# PeakShaver.net
KiCad netlist of a schematic drawn in EAGLE
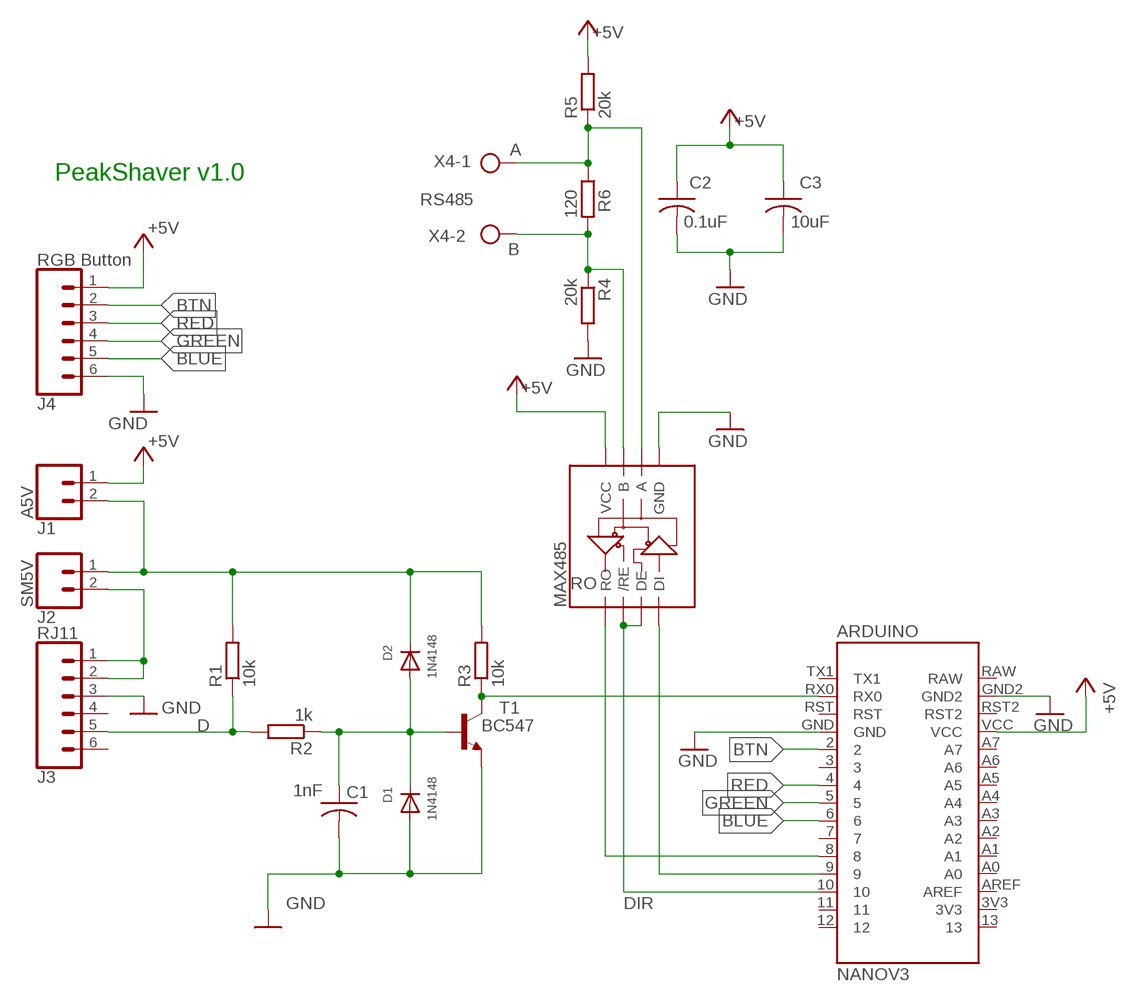
[diagram p0: schematic, sheet 1]

(export (version "E")
  (design (tool "Eeschema 10.0.6"))
  (components
    (comp (ref "ARDUINO")
      (value "NANOV3")
      (footprint "eagle-import:NANOV3")
      (libsource (lib "eagle-import") (part "NANOV3"))
    )
    (comp (ref "C1")
      (value "1nF")
      (footprint "eagle-import:C025-025X050")
      (libsource (lib "eagle-import") (part "C-US025-025X050"))
    )
    (comp (ref "C2")
      (value "0.1uF")
      (footprint "eagle-import:C025-025X050")
      (libsource (lib "eagle-import") (part "C-US025-025X050"))
    )
    (comp (ref "C3")
      (value "10uF")
      (footprint "eagle-import:CAP_RADIAL_2MM")
      (fields
        (field (name "DIGIKEY_PART_NUMBER") "P5178-ND")
        (field (name "MANUFACTURER") "Panasonic Electronic Components")
        (field (name "MPN") "ECA-1HM100")
        (field (name "CREATED_BY") "PCBLayout.com")
      )
      (libsource (lib "eagle-import") (part "ECA-1HM100"))
    )
    (comp (ref "D1")
      (value "1N4148")
      (footprint "eagle-import:DO-1N4148")
      (libsource (lib "eagle-import") (part "DIODEDO-1N4148"))
    )
    (comp (ref "D2")
      (value "1N4148")
      (footprint "eagle-import:DO-1N4148")
      (libsource (lib "eagle-import") (part "DIODEDO-1N4148"))
    )
    (comp (ref "J1")
      (value "A5V")
      (footprint "eagle-import:1X02")
      (libsource (lib "eagle-import") (part "CONN_02"))
    )
    (comp (ref "J2")
      (value "SM5V")
      (footprint "eagle-import:1X02")
      (libsource (lib "eagle-import") (part "CONN_02"))
    )
    (comp (ref "J3")
      (value "RJ11")
      (footprint "eagle-import:RJ11-6")
      (libsource (lib "eagle-import") (part "RJ11-6"))
    )
    (comp (ref "J4")
      (value "RGB Button")
      (footprint "eagle-import:1X06_LOCK")
      (libsource (lib "eagle-import") (part "CONN_06LOCK"))
    )
    (comp (ref "MAX485")
      (value "SPARKFUN-IC-COMMS_RS485")
      (footprint "eagle-import:TEXAS_DIL08")
      (libsource (lib "eagle-import") (part "SPARKFUN-IC-COMMS_RS485"))
    )
    (comp (ref "R1")
      (value "10k")
      (footprint "eagle-import:0207_10")
      (libsource (lib "eagle-import") (part "R-EU_0207/10"))
    )
    (comp (ref "R2")
      (value "1k")
      (footprint "eagle-import:0207_10")
      (libsource (lib "eagle-import") (part "R-EU_0207/10"))
    )
    (comp (ref "R3")
      (value "10k")
      (footprint "eagle-import:0207_10")
      (libsource (lib "eagle-import") (part "R-EU_0207/10"))
    )
    (comp (ref "R4")
      (value "20k")
      (footprint "eagle-import:0207_10")
      (libsource (lib "eagle-import") (part "R-EU_0207/10"))
    )
    (comp (ref "R5")
      (value "20k")
      (footprint "eagle-import:0207_10")
      (libsource (lib "eagle-import") (part "R-EU_0207/10"))
    )
    (comp (ref "R6")
      (value "120")
      (footprint "eagle-import:0207_10")
      (libsource (lib "eagle-import") (part "R-EU_0207/10"))
    )
    (comp (ref "T1")
      (value "BC547")
      (footprint "eagle-import:TO92")
      (libsource (lib "eagle-import") (part "BC547"))
    )
    (comp (ref "X4")
      (value "RS485")
      (footprint "eagle-import:W237-102")
      (fields (field (name "MPN") "237-102"))
      (libsource (lib "eagle-import") (part "W237-102"))
    )
  )
  (nets
    (net (code "1") (name "+5V") (class "Default")
      (node (ref "ARDUINO") (pin "VCC") (pinfunction "VCC_VCC") (pintype "bidirectional"))
      (node (ref "C2") (pin "1") (pinfunction "1_1") (pintype "passive"))
      (node (ref "C3") (pin "1") (pinfunction "1_1") (pintype "passive"))
      (node (ref "J1") (pin "1") (pinfunction "1_1") (pintype "passive"))
      (node (ref "J4") (pin "1") (pinfunction "1_1") (pintype "passive"))
      (node (ref "MAX485") (pin "8") (pinfunction "VCC_8") (pintype "bidirectional"))
      (node (ref "R5") (pin "2") (pinfunction "2_2") (pintype "passive"))
    )
    (net (code "2") (name "/A") (class "Default")
      (node (ref "MAX485") (pin "6") (pinfunction "A_6") (pintype "bidirectional"))
      (node (ref "R5") (pin "1") (pinfunction "1_1") (pintype "passive"))
      (node (ref "R6") (pin "1") (pinfunction "1_1") (pintype "passive"))
      (node (ref "X4") (pin "1") (pinfunction "KL_1") (pintype "passive"))
    )
    (net (code "3") (name "/B") (class "Default")
      (node (ref "MAX485") (pin "7") (pinfunction "B_7") (pintype "bidirectional"))
      (node (ref "R4") (pin "1") (pinfunction "1_1") (pintype "passive"))
      (node (ref "R6") (pin "2") (pinfunction "2_2") (pintype "passive"))
      (node (ref "X4") (pin "2") (pinfunction "KL_2") (pintype "passive"))
    )
    (net (code "4") (name "/D") (class "Default")
      (node (ref "J3") (pin "5") (pinfunction "5_5") (pintype "passive"))
      (node (ref "R1") (pin "1") (pinfunction "1_1") (pintype "passive"))
      (node (ref "R2") (pin "2") (pinfunction "2_2") (pintype "passive"))
    )
    (net (code "5") (name "/DIR") (class "Default")
      (node (ref "ARDUINO") (pin "10") (pinfunction "10_10") (pintype "bidirectional"))
      (node (ref "MAX485") (pin "2") (pinfunction "/RE_2") (pintype "bidirectional"))
      (node (ref "MAX485") (pin "3") (pinfunction "DE_3") (pintype "bidirectional"))
    )
    (net (code "6") (name "/RO") (class "Default")
      (node (ref "ARDUINO") (pin "8") (pinfunction "8_8") (pintype "bidirectional"))
      (node (ref "MAX485") (pin "1") (pinfunction "RO_1") (pintype "bidirectional"))
    )
    (net (code "7") (name "BLUE") (class "Default")
      (node (ref "ARDUINO") (pin "6") (pinfunction "6_6") (pintype "bidirectional"))
      (node (ref "J4") (pin "5") (pinfunction "5_5") (pintype "passive"))
    )
    (net (code "8") (name "BTN") (class "Default")
      (node (ref "ARDUINO") (pin "2") (pinfunction "2_2") (pintype "bidirectional"))
      (node (ref "J4") (pin "2") (pinfunction "2_2") (pintype "passive"))
    )
    (net (code "9") (name "GND") (class "Default")
      (node (ref "ARDUINO") (pin "GND") (pinfunction "GND_GND") (pintype "bidirectional"))
      (node (ref "ARDUINO") (pin "GND2") (pinfunction "GND2_GND2") (pintype "bidirectional"))
      (node (ref "C1") (pin "2") (pinfunction "2_2") (pintype "passive"))
      (node (ref "C2") (pin "2") (pinfunction "2_2") (pintype "passive"))
      (node (ref "C3") (pin "2") (pinfunction "2_2") (pintype "passive"))
      (node (ref "D1") (pin "A") (pinfunction "A_A") (pintype "passive"))
      (node (ref "J3") (pin "3") (pinfunction "3_3") (pintype "passive"))
      (node (ref "J4") (pin "6") (pinfunction "6_6") (pintype "passive"))
      (node (ref "MAX485") (pin "5") (pinfunction "GND_5") (pintype "bidirectional"))
      (node (ref "R4") (pin "2") (pinfunction "2_2") (pintype "passive"))
      (node (ref "T1") (pin "1") (pinfunction "E_1") (pintype "passive"))
    )
    (net (code "10") (name "GREEN") (class "Default")
      (node (ref "ARDUINO") (pin "5") (pinfunction "5_5") (pintype "bidirectional"))
      (node (ref "J4") (pin "4") (pinfunction "4_4") (pintype "passive"))
    )
    (net (code "11") (name "Net-(D2-PadC)") (class "Default")
      (node (ref "D2") (pin "C") (pinfunction "C_C") (pintype "passive"))
      (node (ref "J1") (pin "2") (pinfunction "2_2") (pintype "passive"))
      (node (ref "J2") (pin "1") (pinfunction "1_1") (pintype "passive"))
      (node (ref "R1") (pin "2") (pinfunction "2_2") (pintype "passive"))
      (node (ref "R3") (pin "2") (pinfunction "2_2") (pintype "passive"))
    )
    (net (code "12") (name "Net-(J2-Pad2)") (class "Default")
      (node (ref "J2") (pin "2") (pinfunction "2_2") (pintype "passive"))
      (node (ref "J3") (pin "1") (pinfunction "1_1") (pintype "passive"))
      (node (ref "J3") (pin "2") (pinfunction "2_2") (pintype "passive"))
    )
    (net (code "13") (name "Net-(MAX485-DI)") (class "Default")
      (node (ref "ARDUINO") (pin "9") (pinfunction "9_9") (pintype "bidirectional"))
      (node (ref "MAX485") (pin "4") (pinfunction "DI_4") (pintype "bidirectional"))
    )
    (net (code "14") (name "Net-(T1-B)") (class "Default")
      (node (ref "C1") (pin "1") (pinfunction "1_1") (pintype "passive"))
      (node (ref "D1") (pin "C") (pinfunction "C_C") (pintype "passive"))
      (node (ref "D2") (pin "A") (pinfunction "A_A") (pintype "passive"))
      (node (ref "R2") (pin "1") (pinfunction "1_1") (pintype "passive"))
      (node (ref "T1") (pin "2") (pinfunction "B_2") (pintype "passive"))
    )
    (net (code "15") (name "Net-(T1-C)") (class "Default")
      (node (ref "ARDUINO") (pin "RX0") (pinfunction "RX0_RX0") (pintype "bidirectional"))
      (node (ref "R3") (pin "1") (pinfunction "1_1") (pintype "passive"))
      (node (ref "T1") (pin "3") (pinfunction "C_3") (pintype "passive"))
    )
    (net (code "16") (name "RED") (class "Default")
      (node (ref "ARDUINO") (pin "4") (pinfunction "4_4") (pintype "bidirectional"))
      (node (ref "J4") (pin "3") (pinfunction "3_3") (pintype "passive"))
    )
    (net (code "17") (name "unconnected-(ARDUINO-Pad3)") (class "Default")
      (node (ref "ARDUINO") (pin "3") (pinfunction "3_3") (pintype "bidirectional"))
    )
    (net (code "18") (name "unconnected-(ARDUINO-Pad3V3)") (class "Default")
      (node (ref "ARDUINO") (pin "3V3") (pinfunction "3V3_3V3") (pintype "bidirectional"))
    )
    (net (code "19") (name "unconnected-(ARDUINO-Pad7)") (class "Default")
      (node (ref "ARDUINO") (pin "7") (pinfunction "7_7") (pintype "bidirectional"))
    )
    (net (code "20") (name "unconnected-(ARDUINO-Pad11)") (class "Default")
      (node (ref "ARDUINO") (pin "11") (pinfunction "11_11") (pintype "bidirectional"))
    )
    (net (code "21") (name "unconnected-(ARDUINO-Pad12)") (class "Default")
      (node (ref "ARDUINO") (pin "12") (pinfunction "12_12") (pintype "bidirectional"))
    )
    (net (code "22") (name "unconnected-(ARDUINO-Pad13)") (class "Default")
      (node (ref "ARDUINO") (pin "13") (pinfunction "13_13") (pintype "bidirectional"))
    )
    (net (code "23") (name "unconnected-(ARDUINO-PadA0)") (class "Default")
      (node (ref "ARDUINO") (pin "A0") (pinfunction "A0_A0") (pintype "bidirectional"))
    )
    (net (code "24") (name "unconnected-(ARDUINO-PadA1)") (class "Default")
      (node (ref "ARDUINO") (pin "A1") (pinfunction "A1_A1") (pintype "bidirectional"))
    )
    (net (code "25") (name "unconnected-(ARDUINO-PadA2)") (class "Default")
      (node (ref "ARDUINO") (pin "A2") (pinfunction "A2_A2") (pintype "bidirectional"))
    )
    (net (code "26") (name "unconnected-(ARDUINO-PadA3)") (class "Default")
      (node (ref "ARDUINO") (pin "A3") (pinfunction "A3_A3") (pintype "bidirectional"))
    )
    (net (code "27") (name "unconnected-(ARDUINO-PadA4)") (class "Default")
      (node (ref "ARDUINO") (pin "A4") (pinfunction "A4_A4") (pintype "bidirectional"))
    )
    (net (code "28") (name "unconnected-(ARDUINO-PadA5)") (class "Default")
      (node (ref "ARDUINO") (pin "A5") (pinfunction "A5_A5") (pintype "bidirectional"))
    )
    (net (code "29") (name "unconnected-(ARDUINO-PadA6)") (class "Default")
      (node (ref "ARDUINO") (pin "A6") (pinfunction "A6_A6") (pintype "bidirectional"))
    )
    (net (code "30") (name "unconnected-(ARDUINO-PadA7)") (class "Default")
      (node (ref "ARDUINO") (pin "A7") (pinfunction "A7_A7") (pintype "bidirectional"))
    )
    (net (code "31") (name "unconnected-(ARDUINO-PadAREF)") (class "Default")
      (node (ref "ARDUINO") (pin "AREF") (pinfunction "AREF_AREF") (pintype "bidirectional"))
    )
    (net (code "32") (name "unconnected-(ARDUINO-PadRAW)") (class "Default")
      (node (ref "ARDUINO") (pin "RAW") (pinfunction "RAW_RAW") (pintype "bidirectional"))
    )
    (net (code "33") (name "unconnected-(ARDUINO-PadRST)") (class "Default")
      (node (ref "ARDUINO") (pin "RST") (pinfunction "RST_RST") (pintype "bidirectional"))
    )
    (net (code "34") (name "unconnected-(ARDUINO-PadRST2)") (class "Default")
      (node (ref "ARDUINO") (pin "RST2") (pinfunction "RST2_RST2") (pintype "bidirectional"))
    )
    (net (code "35") (name "unconnected-(ARDUINO-PadTX1)") (class "Default")
      (node (ref "ARDUINO") (pin "TX1") (pinfunction "TX1_TX1") (pintype "bidirectional"))
    )
    (net (code "36") (name "unconnected-(J3-Pad4)") (class "Default")
      (node (ref "J3") (pin "4") (pinfunction "4_4") (pintype "passive"))
    )
    (net (code "37") (name "unconnected-(J3-Pad6)") (class "Default")
      (node (ref "J3") (pin "6") (pinfunction "6_6") (pintype "passive"))
    )
  )
)
